# ideal-diode.net
KiCad netlist of a schematic drawn in Altium Designer
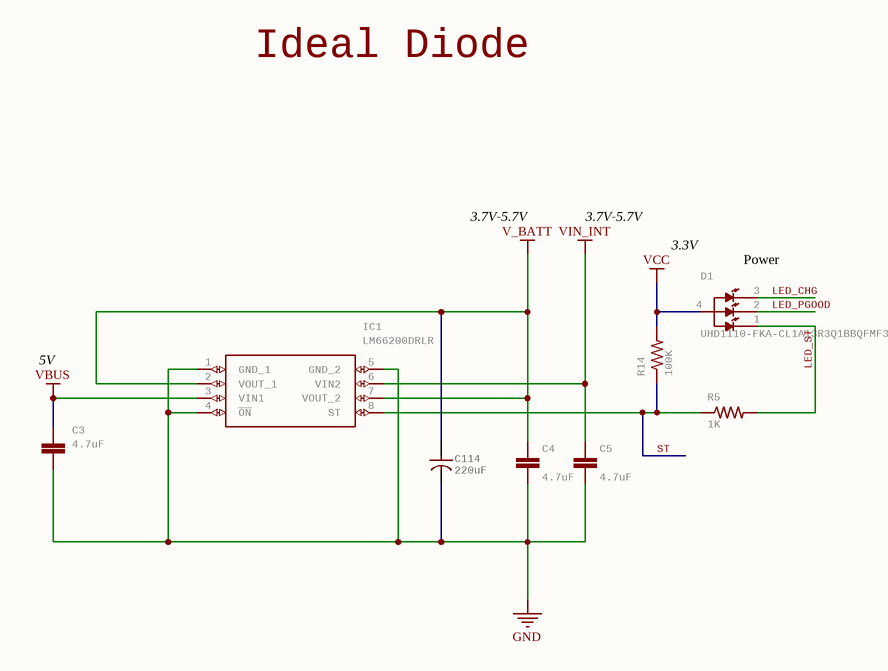
[diagram p0: ideal-diode.SchDoc]

(export (version "E")
  (design (tool "Eeschema 10.0.6"))
  (components
    (comp (ref "C3")
      (value "4.7uF")
      (footprint "0402-CAP")
      (description "CapacitorStandard 0603 ceramic capacitor, and 0.1\" leaded capacitor.")
      (fields (field (name "MPN") "JMK105BBJ475MV-F"))
      (libsource (lib "rt10") (part "CAP0402-CAP"))
    )
    (comp (ref "C4")
      (value "4.7uF")
      (footprint "0402-CAP")
      (description "CapacitorStandard 0603 ceramic capacitor, and 0.1\" leaded capacitor.")
      (fields (field (name "MPN") "JMK105BBJ475MV-F"))
      (libsource (lib "rt10") (part "CAP0402-CAP"))
    )
    (comp (ref "C5")
      (value "4.7uF")
      (footprint "0402-CAP")
      (description "CapacitorStandard 0603 ceramic capacitor, and 0.1\" leaded capacitor.")
      (fields (field (name "MPN") "JMK105BBJ475MV-F"))
      (libsource (lib "rt10") (part "CAP0402-CAP"))
    )
    (comp (ref "C114")
      (value "220uF")
      (footprint "CAP-TANT-1411")
      (fields (field (name "PART NUMBER") "F930J227MBA"))
      (libsource (lib "rt10") (part "CAP_POL"))
    )
    (comp (ref "D1")
      (value "UHD1110-FKA-CL1A13R3Q1BBQFMF3")
      (footprint "LED_UHD1110-FKA-CL1A13R3Q1BBQFMF3")
      (description "LED RGB SMD, SIZE 1 X 1 mm Check availability")
      (fields (field (name "MF") "Cree Inc.") (field (name "MPN") "UHD1110-FKA-CL1A13r3q1BBQFMF3"))
      (libsource (lib "rt10") (part "UHD1110-FKA-CL1A13R3Q1BBQFMF3"))
    )
    (comp (ref "IC1")
      (value "LM66200DRLR")
      (footprint "SOTFL50P160X60-8N")
      (description "1.6-V to 5.5-V, 40-m, 2.5-A, low-IQ, dual ideal diode   Source:  Datasheet")
      (fields (field (name "MOUSER_PART_NUMBER") "595-LM66200DRLR"))
      (libsource (lib "rt10") (part "LM66200DRLR"))
    )
    (comp (ref "R5")
      (value "1K")
      (footprint "0402-RES")
      (description "ResistorBasic schematic elements and footprints for 0603, 1206, and PTH resistors.")
      (fields (field (name "MPN") "CRCW04021K00FKEDC"))
      (libsource (lib "rt10") (part "RESISTOR0402-RES"))
    )
    (comp (ref "R14")
      (value "100K")
      (footprint "0402-RES")
      (description "ResistorBasic schematic elements and footprints for 0603, 1206, and PTH resistors.")
      (fields (field (name "MPN") "AC0402FR-07100KL"))
      (libsource (lib "rt10") (part "RESISTOR0402-RES"))
    )
  )
  (nets
    (net (code "1") (name "/LED_CHG") (class "Default")
      (node (ref "D1") (pin "3") (pinfunction "RED_3") (pintype "passive"))
    )
    (net (code "2") (name "/LED_PGOOD") (class "Default")
      (node (ref "D1") (pin "2") (pinfunction "GREEN_2") (pintype "passive"))
    )
    (net (code "3") (name "/LED_ST") (class "Default")
      (node (ref "D1") (pin "1") (pinfunction "BLUE_1") (pintype "passive"))
      (node (ref "R5") (pin "2") (pinfunction "2_2") (pintype "passive"))
    )
    (net (code "4") (name "/ST") (class "Default")
      (node (ref "IC1") (pin "8") (pinfunction "ST_8") (pintype "bidirectional"))
      (node (ref "R14") (pin "1") (pinfunction "1_1") (pintype "passive"))
      (node (ref "R5") (pin "1") (pinfunction "1_1") (pintype "passive"))
    )
    (net (code "5") (name "GND") (class "Default")
      (node (ref "C114") (pin "2") (pinfunction "2_2") (pintype "passive"))
      (node (ref "C3") (pin "1") (pinfunction "1_1") (pintype "passive"))
      (node (ref "C4") (pin "1") (pinfunction "1_1") (pintype "passive"))
      (node (ref "C5") (pin "1") (pinfunction "1_1") (pintype "passive"))
      (node (ref "IC1") (pin "1") (pinfunction "GND_1_1") (pintype "bidirectional"))
      (node (ref "IC1") (pin "4") (pinfunction "~{ON}_4") (pintype "bidirectional"))
      (node (ref "IC1") (pin "5") (pinfunction "GND_2_5") (pintype "bidirectional"))
    )
    (net (code "6") (name "VBUS") (class "Default")
      (node (ref "C3") (pin "2") (pinfunction "2_2") (pintype "passive"))
      (node (ref "IC1") (pin "3") (pinfunction "VIN1_3") (pintype "bidirectional"))
    )
    (net (code "7") (name "VCC") (class "Default")
      (node (ref "D1") (pin "4") (pinfunction "ANODE_4") (pintype "passive"))
      (node (ref "R14") (pin "2") (pinfunction "2_2") (pintype "passive"))
    )
    (net (code "8") (name "VIN_INT") (class "Default")
      (node (ref "C5") (pin "2") (pinfunction "2_2") (pintype "passive"))
      (node (ref "IC1") (pin "6") (pinfunction "VIN2_6") (pintype "bidirectional"))
    )
    (net (code "9") (name "V_BATT") (class "Default")
      (node (ref "C114") (pin "1") (pinfunction "1_1") (pintype "passive"))
      (node (ref "C4") (pin "2") (pinfunction "2_2") (pintype "passive"))
      (node (ref "IC1") (pin "2") (pinfunction "VOUT_1_2") (pintype "bidirectional"))
      (node (ref "IC1") (pin "7") (pinfunction "VOUT_2_7") (pintype "bidirectional"))
    )
  )
)
